# TSAL_Inverters.net
KiCad netlist of a schematic drawn in Altium Designer
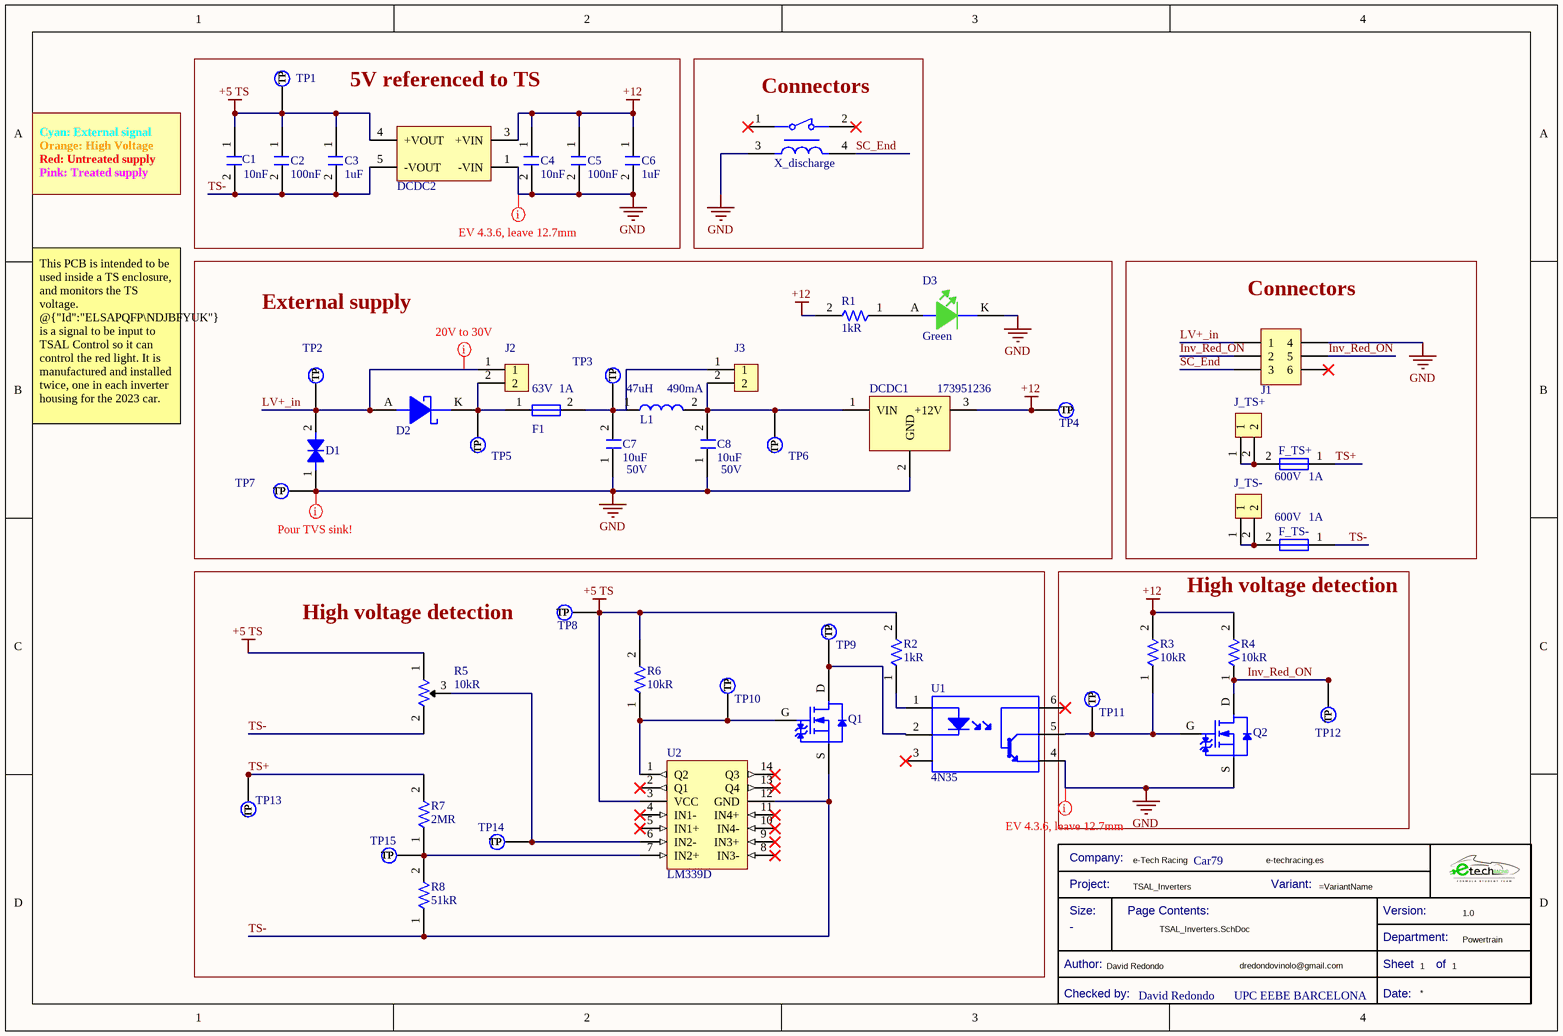
[diagram p0: TSAL_Inverters.SchDoc]

(export (version "E")
  (design (tool "Eeschema 10.0.6"))
  (components
    (comp (ref "*")
      (value "Title Block_template")
      (description "Standard Title Block")
      (fields
        (field (name "SIZE") "-")
        (field (name ".CREATOR") "GP")
        (field (name ".PCBCHECK") "GP")
        (field (name ".SCHCHECK") "GP")
      )
      (libsource (lib "e-Tech_Racing") (part "Title Block_template"))
    )
    (comp (ref "C1")
      (value "885012207092")
      (footprint "C0805FNPC-R")
      (description "Cap, 0.01ΜF, 50V, 10%, X7R, 0805")
      (fields
        (field (name "TOLERANCE") "10%")
        (field (name "CAPACITANCE") "10nF")
        (field (name ".CREATOR") "DR")
      )
      (libsource (lib "Passives") (part "C10n-50V-0805FNPC-X7R"))
    )
    (comp (ref "C2")
      (value "885012207098")
      (footprint "C0805FNPC-R")
      (description "Cap, 0.1ΜF, 50V, 10%, X7R, 0805")
      (fields
        (field (name "TOLERANCE") "10%")
        (field (name "CAPACITANCE") "100nF")
        (field (name ".CREATOR") "DR")
      )
      (libsource (lib "Passives") (part "C100n-50V-0805FNPC-X7R"))
    )
    (comp (ref "C3")
      (value "885012207103")
      (footprint "C0805FNPC-R")
      (fields
        (field (name "TOLERANCE") "10%")
        (field (name "CAPACITANCE") "1uF")
        (field (name ".CREATOR") "GP")
      )
      (libsource (lib "Passives") (part "C1u-50V-0805FNPC-X7R"))
    )
    (comp (ref "C4")
      (value "885012207092")
      (footprint "C0805FNPC-R")
      (description "Cap, 0.01ΜF, 50V, 10%, X7R, 0805")
      (fields
        (field (name "TOLERANCE") "10%")
        (field (name "CAPACITANCE") "10nF")
        (field (name ".CREATOR") "DR")
      )
      (libsource (lib "Passives") (part "C10n-50V-0805FNPC-X7R"))
    )
    (comp (ref "C5")
      (value "885012207098")
      (footprint "C0805FNPC-R")
      (description "Cap, 0.1ΜF, 50V, 10%, X7R, 0805")
      (fields
        (field (name "TOLERANCE") "10%")
        (field (name "CAPACITANCE") "100nF")
        (field (name ".CREATOR") "DR")
      )
      (libsource (lib "Passives") (part "C100n-50V-0805FNPC-X7R"))
    )
    (comp (ref "C6")
      (value "885012207103")
      (footprint "C0805FNPC-R")
      (fields
        (field (name "TOLERANCE") "10%")
        (field (name "CAPACITANCE") "1uF")
        (field (name ".CREATOR") "GP")
      )
      (libsource (lib "Passives") (part "C1u-50V-0805FNPC-X7R"))
    )
    (comp (ref "C7")
      (value "GRJ32ER71H106KE11L")
      (footprint "C10u-50V-1210FNPMLCC-X7R")
      (description "Multilayer Ceramic Capacitors MLCC - SMD/SMT 1210 10uF 50volts X7R +/-10% Soft Term")
      (fields
        (field (name "MANUFACTURER") "Murata")
        (field (name "VOLTAGE RATING") "50V")
        (field (name "TOLERANCE") "10%")
        (field (name "CAPACITANCE") "10uF")
        (field (name ".CREATOR") "DR")
      )
      (libsource (lib "Passives") (part "C10u-50V-1210FNPMLCC-X7R"))
    )
    (comp (ref "C8")
      (value "GRJ32ER71H106KE11L")
      (footprint "C10u-50V-1210FNPMLCC-X7R")
      (description "Multilayer Ceramic Capacitors MLCC - SMD/SMT 1210 10uF 50volts X7R +/-10% Soft Term")
      (fields
        (field (name "MANUFACTURER") "Murata")
        (field (name "VOLTAGE RATING") "50V")
        (field (name "TOLERANCE") "10%")
        (field (name "CAPACITANCE") "10uF")
        (field (name ".CREATOR") "DR")
      )
      (libsource (lib "Passives") (part "C10u-50V-1210FNPMLCC-X7R"))
    )
    (comp (ref "D1")
      (value "824551301")
      (footprint "DTVS-DO-214AB")
      (description "TVS diode [Würth Elektronik] 824551301 TVS diode")
      (fields (field (name "MANUFACTURER") "Wurth Electronics") (field (name ".CREATOR") "DO"))
      (libsource (lib "Filter components") (part "DTVS-40V-DO-214AB"))
    )
    (comp (ref "D2")
      (value "MBR0530")
      (footprint "DSC-SOD123")
      (description "VR=30V IF=500mA 30pF P=410mW")
      (fields (field (name ".CREATOR") "GP"))
      (libsource (lib "Filter components") (part "DSC-0.5/30-SOD123"))
    )
    (comp (ref "D3")
      (value "150080VS75000")
      (footprint "LED_0805_WE")
      (description "Led, Green, 570 Nm, 2 V, 30 Ma, 40 Mcd Rohs Compliant: Yes")
      (fields (field (name "COLOR") "Green") (field (name ".CREATOR") "DR"))
      (libsource (lib "Semiconductor") (part "LEDVS-0805-40"))
    )
    (comp (ref "DCDC1")
      (value "173951236")
      (footprint "DCDC_Magi3c")
      (description "Fdsm Fixed Step Down Regulator M")
      (libsource (lib "Semiconductor") (part "DCDC-36V/12V-0.5A"))
    )
    (comp (ref "DCDC2")
      (value "RNM-1205S/P")
      (footprint "DCDC_RNM-XX05S/P")
      (description "1W DC/DC-Converter 'ECONOLINE' DIP6 1kV unreg; V. In: 12; V. Out: 05; mA. Out: 200")
      (libsource (lib "Semiconductor") (part "DCDC_RNM-1205S/P"))
    )
    (comp (ref "F1")
      (value "0437001.WRA")
      (footprint "Fuse_1206")
      (description "Fuse Chip Fast Acting 1A 63V SMD Solder Pad 1206 Ceramic T/R Automotive")
      (fields
        (field (name "MANUFACTURER") "Littelfuse")
        (field (name "CURRENT RATING") "1A")
        (field (name "VOLTAGE RATING (DC)") "63V")
        (field (name ".CREATOR") "DO")
      )
      (libsource (lib "Filter components") (part "Fuse_1A_63V_1206"))
    )
    (comp (ref "F_TS+")
      (value "485001")
      (footprint "Fuse_485001")
      (description "Surface Mount Fuses 600V 1A Fast Acting")
      (fields
        (field (name "VOLTAGE RATING (DC)") "600V")
        (field (name "CURRENT RATING") "1A")
        (field (name ".CREATOR") "DO")
      )
      (libsource (lib "Filter components") (part "Fuse_1A_600V"))
    )
    (comp (ref "F_TS-")
      (value "485001")
      (footprint "Fuse_485001")
      (description "Surface Mount Fuses 600V 1A Fast Acting")
      (fields
        (field (name "VOLTAGE RATING (DC)") "600V")
        (field (name "CURRENT RATING") "1A")
        (field (name ".CREATOR") "DO")
      )
      (libsource (lib "Filter components") (part "Fuse_1A_600V"))
    )
    (comp (ref "J1")
      (value "J_NanoFit_2x3")
      (footprint "J_NanoFit_2x3")
      (libsource (lib "Electromechanical") (part "J_NanoFit_2x3"))
    )
    (comp (ref "J2")
      (value "61300211121")
      (footprint "J_Pinheader_1x2")
      (description "CONN HEADER 2 POS 2.54")
      (fields (field (name "MANUFACTURER") "Molex") (field (name ".CREATOR") "GP"))
      (libsource (lib "Electromechanical") (part "J_Jumper"))
    )
    (comp (ref "J3")
      (value "61300211121")
      (footprint "J_Pinheader_1x2")
      (description "CONN HEADER 2 POS 2.54")
      (fields (field (name "MANUFACTURER") "Molex") (field (name ".CREATOR") "GP"))
      (libsource (lib "Electromechanical") (part "J_Jumper"))
    )
    (comp (ref "J_TS+")
      (value "436500215")
      (footprint "J_MicroFit_2x1")
      (description "Header 1 Row Vertical Polarizing Peg 2 Pin SMT/Glow Wire Compatible Tin Plate")
      (libsource (lib "Electromechanical") (part "J_MicroFit_2x1"))
    )
    (comp (ref "J_TS-")
      (value "436500215")
      (footprint "J_MicroFit_2x1")
      (description "Header 1 Row Vertical Polarizing Peg 2 Pin SMT/Glow Wire Compatible Tin Plate")
      (libsource (lib "Electromechanical") (part "J_MicroFit_2x1"))
    )
    (comp (ref "L1")
      (value "CDC5D23BNP-470KC")
      (footprint "L_47u-490mA_CF")
      (description "Inductor Power Unshielded Wirewound 47uH 10% 100KHz Ferrite 490mA 546mOhm DCR T/R")
      (fields
        (field (name "MANUFACTURER") "Sumida")
        (field (name "TOLERANCE") "10%")
        (field (name "CURRENT RATING") "490mA")
        (field (name "INDUCTANCE") "47uH")
        (field (name ".CREATOR") "GP")
      )
      (libsource (lib "Passives") (part "L_47u-490mA_CF"))
    )
    (comp (ref "Q1")
      (value "SQ2318BES-T1_GE3")
      (footprint "TRT-NCH-3/35-CPH")
      (description "Automotive N-channel 40 V (d-s) 175C Mosfet SOT-23")
      (fields (field (name ".CREATOR") "DO"))
      (libsource (lib "Semiconductor") (part "TRT-NCH-8/40-SQ"))
    )
    (comp (ref "Q2")
      (value "SQ2318BES-T1_GE3")
      (footprint "TRT-NCH-3/35-CPH")
      (description "Automotive N-channel 40 V (d-s) 175C Mosfet SOT-23")
      (fields (field (name ".CREATOR") "DO"))
      (libsource (lib "Semiconductor") (part "TRT-NCH-8/40-SQ"))
    )
    (comp (ref "R1")
      (value "CR0805-JW-102ELF")
      (footprint "R0805FTK")
      (description "Res Thick Film 0805 1K Ohm 5% 1/8W ±200ppm/°C Molded SMD SMD Paper Tape on Plastic Reel")
      (fields
        (field (name "TOLERANCE") "5%")
        (field (name "RESISTANCE") "1kR")
        (field (name ".CREATOR") "GP")
      )
      (libsource (lib "Passives") (part "R1k-0805FTK"))
    )
    (comp (ref "R2")
      (value "CR0805-JW-102ELF")
      (footprint "R0805FTK")
      (description "Res Thick Film 0805 1K Ohm 5% 1/8W ±200ppm/°C Molded SMD SMD Paper Tape on Plastic Reel")
      (fields
        (field (name "TOLERANCE") "5%")
        (field (name "RESISTANCE") "1kR")
        (field (name ".CREATOR") "GP")
      )
      (libsource (lib "Passives") (part "R1k-0805FTK"))
    )
    (comp (ref "R3")
      (value "CR0805-JW-103ELF")
      (footprint "R0805FTK")
      (fields
        (field (name "TOLERANCE") "5%")
        (field (name "RESISTANCE") "10kR")
        (field (name ".CREATOR") "DR")
      )
      (libsource (lib "Passives") (part "R10k-0805FTK"))
    )
    (comp (ref "R4")
      (value "CR0805-JW-103ELF")
      (footprint "R0805FTK")
      (fields
        (field (name "TOLERANCE") "5%")
        (field (name "RESISTANCE") "10kR")
        (field (name ".CREATOR") "DR")
      )
      (libsource (lib "Passives") (part "R10k-0805FTK"))
    )
    (comp (ref "R5")
      (value "3296W-1-103LF")
      (footprint "R10k-VTR")
      (description "Trimmer, Cermet, Rest 10 Kilohms, PCB, 25 Turns, Pwr-Rtg 0.5W, 3296 Series")
      (fields
        (field (name "MANUFACTURER") "Bourns")
        (field (name "TOLERANCE") "10%")
        (field (name "RESISTANCE") "10kR")
        (field (name ".CREATOR") "DO")
      )
      (libsource (lib "Passives") (part "R10k-VTR"))
    )
    (comp (ref "R6")
      (value "CR0805-JW-103ELF")
      (footprint "R0805FTK")
      (fields
        (field (name "TOLERANCE") "5%")
        (field (name "RESISTANCE") "10kR")
        (field (name ".CREATOR") "DR")
      )
      (libsource (lib "Passives") (part "R10k-0805FTK"))
    )
    (comp (ref "R7")
      (value "R2M-2512FTK")
      (footprint "R2512FTK")
      (description "Current Sense Resistors - SMD 3watts .002ohms 1%")
      (fields
        (field (name "MANUFACTURER") "Vishay Dale")
        (field (name "MANUFACTURER PART NUMBER") "WSLP25122L000FEA")
        (field (name "RESISTANCE") "2MR")
      )
      (libsource (lib "Passives") (part "R2M-2512FTK"))
    )
    (comp (ref "R8")
      (value "CRCW120610K0FKEA")
      (footprint "R1206FTK-W")
      (description "Res Thick Film 1206 51K Ohm 1% 1/4W ±100ppm/°C Molded SMD SMD Punched Carrier T/R")
      (fields
        (field (name "MANUFACTURER") "Panasonic")
        (field (name "MANUFACTURER PART NUMBER") "ERJ-S08F5102V")
        (field (name "RESISTANCE") "51kR")
        (field (name ".CREATOR") "DO")
      )
      (libsource (lib "Passives") (part "R51k-1206FTK"))
    )
    (comp (ref "TP1")
      (value "TestPoint")
      (footprint "TestPoint")
      (description "Test Point 1x1 mm")
      (fields (field (name ".CREATOR") "GP") (field (name ".PCBCHECK") "GP") (field (name ".SCHCHECK") "GP"))
      (libsource (lib "e-Tech_Racing") (part "TestPoint"))
    )
    (comp (ref "TP2")
      (value "TestPoint")
      (footprint "TestPoint")
      (description "Test Point 1x1 mm")
      (fields (field (name ".CREATOR") "GP") (field (name ".PCBCHECK") "GP") (field (name ".SCHCHECK") "GP"))
      (libsource (lib "e-Tech_Racing") (part "TestPoint"))
    )
    (comp (ref "TP3")
      (value "TestPoint")
      (footprint "TestPoint")
      (description "Test Point 1x1 mm")
      (fields (field (name ".CREATOR") "GP") (field (name ".PCBCHECK") "GP") (field (name ".SCHCHECK") "GP"))
      (libsource (lib "e-Tech_Racing") (part "TestPoint"))
    )
    (comp (ref "TP4")
      (value "TestPoint")
      (footprint "TestPoint")
      (description "Test Point 1x1 mm")
      (fields (field (name ".CREATOR") "GP") (field (name ".PCBCHECK") "GP") (field (name ".SCHCHECK") "GP"))
      (libsource (lib "e-Tech_Racing") (part "TestPoint"))
    )
    (comp (ref "TP5")
      (value "TestPoint")
      (footprint "TestPoint")
      (description "Test Point 1x1 mm")
      (fields (field (name ".CREATOR") "GP") (field (name ".PCBCHECK") "GP") (field (name ".SCHCHECK") "GP"))
      (libsource (lib "e-Tech_Racing") (part "TestPoint"))
    )
    (comp (ref "TP6")
      (value "TestPoint")
      (footprint "TestPoint")
      (description "Test Point 1x1 mm")
      (fields (field (name ".CREATOR") "GP") (field (name ".PCBCHECK") "GP") (field (name ".SCHCHECK") "GP"))
      (libsource (lib "e-Tech_Racing") (part "TestPoint"))
    )
    (comp (ref "TP7")
      (value "TestPoint")
      (footprint "TestPoint")
      (description "Test Point 1x1 mm")
      (fields (field (name ".CREATOR") "GP") (field (name ".PCBCHECK") "GP") (field (name ".SCHCHECK") "GP"))
      (libsource (lib "e-Tech_Racing") (part "TestPoint"))
    )
    (comp (ref "TP8")
      (value "TestPoint")
      (footprint "TestPoint")
      (description "Test Point 1x1 mm")
      (fields (field (name ".CREATOR") "GP") (field (name ".PCBCHECK") "GP") (field (name ".SCHCHECK") "GP"))
      (libsource (lib "e-Tech_Racing") (part "TestPoint"))
    )
    (comp (ref "TP9")
      (value "TestPoint")
      (footprint "TestPoint")
      (description "Test Point 1x1 mm")
      (fields (field (name ".CREATOR") "GP") (field (name ".PCBCHECK") "GP") (field (name ".SCHCHECK") "GP"))
      (libsource (lib "e-Tech_Racing") (part "TestPoint"))
    )
    (comp (ref "TP10")
      (value "TestPoint")
      (footprint "TestPoint")
      (description "Test Point 1x1 mm")
      (fields (field (name ".CREATOR") "GP") (field (name ".PCBCHECK") "GP") (field (name ".SCHCHECK") "GP"))
      (libsource (lib "e-Tech_Racing") (part "TestPoint"))
    )
    (comp (ref "TP11")
      (value "TestPoint")
      (footprint "TestPoint")
      (description "Test Point 1x1 mm")
      (fields (field (name ".CREATOR") "GP") (field (name ".PCBCHECK") "GP") (field (name ".SCHCHECK") "GP"))
      (libsource (lib "e-Tech_Racing") (part "TestPoint"))
    )
    (comp (ref "TP12")
      (value "TestPoint")
      (footprint "TestPoint")
      (description "Test Point 1x1 mm")
      (fields (field (name ".CREATOR") "GP") (field (name ".PCBCHECK") "GP") (field (name ".SCHCHECK") "GP"))
      (libsource (lib "e-Tech_Racing") (part "TestPoint"))
    )
    (comp (ref "TP13")
      (value "TestPoint")
      (footprint "TestPoint")
      (description "Test Point 1x1 mm")
      (fields (field (name ".CREATOR") "GP") (field (name ".PCBCHECK") "GP") (field (name ".SCHCHECK") "GP"))
      (libsource (lib "e-Tech_Racing") (part "TestPoint"))
    )
    (comp (ref "TP14")
      (value "TestPoint")
      (footprint "TestPoint")
      (description "Test Point 1x1 mm")
      (fields (field (name ".CREATOR") "GP") (field (name ".PCBCHECK") "GP") (field (name ".SCHCHECK") "GP"))
      (libsource (lib "e-Tech_Racing") (part "TestPoint"))
    )
    (comp (ref "TP15")
      (value "TestPoint")
      (footprint "TestPoint")
      (description "Test Point 1x1 mm")
      (fields (field (name ".CREATOR") "GP") (field (name ".PCBCHECK") "GP") (field (name ".SCHCHECK") "GP"))
      (libsource (lib "e-Tech_Racing") (part "TestPoint"))
    )
    (comp (ref "U1")
      (value "4N35")
      (footprint "Optocoupler_4N35")
      (description "Optocoupler DC-IN 1-CH Transistor With Base DC-OUT 6-Pin PDIP SMD T/R")
      (fields
        (field (name "MANUFACTURER") "Vishay Lite-On")
        (field (name "MANUFACTURER PART NUMBER") "CNY17-4S-TA1")
        (field (name ".CREATOR") "DO")
      )
      (libsource (lib "Semiconductor") (part "Optocoupler_4N35"))
    )
    (comp (ref "U2")
      (value "LM339D")
      (footprint "Array_4_Amp_LM339D")
      (description "Comparator Quad ±18V/36V 14-Pin SOIC Tube")
      (fields
        (field (name "MANUFACTURER") "Texas Instruments")
        (field (name "MANUFACTURER PART NUMBER") "LM339D")
        (field (name ".CREATOR") "DO")
      )
      (libsource (lib "Integrated circuits") (part "Array_4_Amp_LM339D"))
    )
    (comp (ref "X_discharge")
      (value "DBR72410FU")
      (footprint "Relay_DAR72410FU")
      (description "Relay, Reed Switch, SPNC, Rhodium Cntcts, 24VDC, 10kV Isol., PCB Mnt/Coil Conn./FL HV")
      (fields (field (name "MANUFACTURER") "Cynergy3") (field (name "MANUFACTURER PART NUMBER") "DBR72410F"))
      (libsource (lib "Electromechanical") (part "Relay_DBR72410FU"))
    )
  )
  (nets
    (net (code "1") (name "+5 TS") (class "Default")
      (node (ref "C1") (pin "1") (pinfunction "1_1") (pintype "passive"))
      (node (ref "C2") (pin "1") (pinfunction "1_1") (pintype "passive"))
      (node (ref "C3") (pin "1") (pinfunction "1_1") (pintype "passive"))
      (node (ref "DCDC2") (pin "4") (pinfunction "+VOUT_4") (pintype "passive"))
      (node (ref "R2") (pin "2") (pinfunction "2_2") (pintype "passive"))
      (node (ref "R5") (pin "1") (pinfunction "2_1") (pintype "passive"))
      (node (ref "R6") (pin "2") (pinfunction "2_2") (pintype "passive"))
      (node (ref "TP1") (pin "1") (pinfunction "TP_1") (pintype "passive"))
      (node (ref "TP8") (pin "1") (pinfunction "TP_1") (pintype "passive"))
      (node (ref "U2") (pin "3") (pinfunction "VCC_3") (pintype "power_in"))
    )
    (net (code "2") (name "+12") (class "Default")
      (node (ref "C4") (pin "1") (pinfunction "1_1") (pintype "passive"))
      (node (ref "C5") (pin "1") (pinfunction "1_1") (pintype "passive"))
      (node (ref "C6") (pin "1") (pinfunction "1_1") (pintype "passive"))
      (node (ref "DCDC1") (pin "3") (pinfunction "+12V_3") (pintype "passive"))
      (node (ref "DCDC2") (pin "3") (pinfunction "+VIN_3") (pintype "passive"))
      (node (ref "R1") (pin "2") (pinfunction "2_2") (pintype "passive"))
      (node (ref "R3") (pin "2") (pinfunction "2_2") (pintype "passive"))
      (node (ref "R4") (pin "2") (pinfunction "2_2") (pintype "passive"))
      (node (ref "TP4") (pin "1") (pinfunction "TP_1") (pintype "passive"))
    )
    (net (code "3") (name "/Inv_Red_ON") (class "Default")
      (node (ref "J1") (pin "2") (pinfunction "2_2") (pintype "passive"))
      (node (ref "J1") (pin "5") (pinfunction "5_5") (pintype "passive"))
      (node (ref "Q2") (pin "D") (pinfunction "D_D") (pintype "passive"))
      (node (ref "R4") (pin "1") (pinfunction "1_1") (pintype "passive"))
      (node (ref "TP12") (pin "1") (pinfunction "TP_1") (pintype "passive"))
    )
    (net (code "4") (name "/LV+_in") (class "Default")
      (node (ref "D1") (pin "2") (pinfunction "2_2") (pintype "passive"))
      (node (ref "D2") (pin "A") (pinfunction "A_A") (pintype "passive"))
      (node (ref "J1") (pin "1") (pinfunction "1_1") (pintype "passive"))
      (node (ref "J2") (pin "1") (pinfunction "1_1") (pintype "passive"))
      (node (ref "TP2") (pin "1") (pinfunction "TP_1") (pintype "passive"))
    )
    (net (code "5") (name "/SC_End") (class "Default")
      (node (ref "J1") (pin "3") (pinfunction "3_3") (pintype "passive"))
      (node (ref "X_discharge") (pin "4") (pinfunction "4_4") (pintype "passive"))
    )
    (net (code "6") (name "/TS+") (class "Default")
      (node (ref "F_TS+") (pin "1") (pinfunction "1_1") (pintype "passive"))
      (node (ref "R7") (pin "2") (pinfunction "2_2") (pintype "passive"))
      (node (ref "TP13") (pin "1") (pinfunction "TP_1") (pintype "passive"))
    )
    (net (code "7") (name "/TS-") (class "Default")
      (node (ref "C1") (pin "2") (pinfunction "2_2") (pintype "passive"))
      (node (ref "C2") (pin "2") (pinfunction "2_2") (pintype "passive"))
      (node (ref "C3") (pin "2") (pinfunction "2_2") (pintype "passive"))
      (node (ref "DCDC2") (pin "5") (pinfunction "-VOUT_5") (pintype "passive"))
      (node (ref "F_TS-") (pin "1") (pinfunction "1_1") (pintype "passive"))
      (node (ref "Q1") (pin "S") (pinfunction "S_S") (pintype "passive"))
      (node (ref "R5") (pin "2") (pinfunction "2_2") (pintype "passive"))
      (node (ref "R8") (pin "1") (pinfunction "1_1") (pintype "passive"))
      (node (ref "U2") (pin "12") (pinfunction "GND_12") (pintype "power_in"))
    )
    (net (code "8") (name "GND") (class "Default")
      (node (ref "C4") (pin "2") (pinfunction "2_2") (pintype "passive"))
      (node (ref "C5") (pin "2") (pinfunction "2_2") (pintype "passive"))
      (node (ref "C6") (pin "2") (pinfunction "2_2") (pintype "passive"))
      (node (ref "C7") (pin "1") (pinfunction "1_1") (pintype "passive"))
      (node (ref "C8") (pin "1") (pinfunction "1_1") (pintype "passive"))
      (node (ref "D1") (pin "1") (pinfunction "1_1") (pintype "passive"))
      (node (ref "D3") (pin "K") (pinfunction "K_K") (pintype "passive"))
      (node (ref "DCDC1") (pin "2") (pinfunction "GND_2") (pintype "passive"))
      (node (ref "DCDC2") (pin "1") (pinfunction "-VIN_1") (pintype "passive"))
      (node (ref "J1") (pin "4") (pinfunction "4_4") (pintype "passive"))
      (node (ref "Q2") (pin "S") (pinfunction "S_S") (pintype "passive"))
      (node (ref "TP7") (pin "1") (pinfunction "TP_1") (pintype "passive"))
      (node (ref "U1") (pin "4") (pinfunction "E_4") (pintype "passive"))
      (node (ref "X_discharge") (pin "3") (pinfunction "3_3") (pintype "passive"))
    )
    (net (code "9") (name "Net-(D3-PadA)") (class "Default")
      (node (ref "D3") (pin "A") (pinfunction "A_A") (pintype "passive"))
      (node (ref "R1") (pin "1") (pinfunction "1_1") (pintype "passive"))
    )
    (net (code "10") (name "Net-(DCDC1-VIN)") (class "Default")
      (node (ref "C8") (pin "2") (pinfunction "2_2") (pintype "passive"))
      (node (ref "DCDC1") (pin "1") (pinfunction "VIN_1") (pintype "passive"))
      (node (ref "J3") (pin "2") (pinfunction "2_2") (pintype "passive"))
      (node (ref "L1") (pin "2") (pinfunction "2_2") (pintype "passive"))
      (node (ref "TP6") (pin "1") (pinfunction "TP_1") (pintype "passive"))
    )
    (net (code "11") (name "Net-(F_TS+-Pad2)") (class "Default")
      (node (ref "F_TS+") (pin "2") (pinfunction "2_2") (pintype "passive"))
      (node (ref "J_TS+") (pin "1") (pinfunction "1_1") (pintype "passive"))
      (node (ref "J_TS+") (pin "2") (pinfunction "2_2") (pintype "passive"))
    )
    (net (code "12") (name "Net-(F_TS--Pad2)") (class "Default")
      (node (ref "F_TS-") (pin "2") (pinfunction "2_2") (pintype "passive"))
      (node (ref "J_TS-") (pin "1") (pinfunction "1_1") (pintype "passive"))
      (node (ref "J_TS-") (pin "2") (pinfunction "2_2") (pintype "passive"))
    )
    (net (code "13") (name "Net-(TP3-TP)") (class "Default")
      (node (ref "C7") (pin "2") (pinfunction "2_2") (pintype "passive"))
      (node (ref "F1") (pin "2") (pinfunction "2_2") (pintype "passive"))
      (node (ref "J3") (pin "1") (pinfunction "1_1") (pintype "passive"))
      (node (ref "L1") (pin "1") (pinfunction "1_1") (pintype "passive"))
      (node (ref "TP3") (pin "1") (pinfunction "TP_1") (pintype "passive"))
    )
    (net (code "14") (name "Net-(TP5-TP)") (class "Default")
      (node (ref "D2") (pin "K") (pinfunction "K_K") (pintype "passive"))
      (node (ref "F1") (pin "1") (pinfunction "1_1") (pintype "passive"))
      (node (ref "J2") (pin "2") (pinfunction "2_2") (pintype "passive"))
      (node (ref "TP5") (pin "1") (pinfunction "TP_1") (pintype "passive"))
    )
    (net (code "15") (name "Net-(TP9-TP)") (class "Default")
      (node (ref "Q1") (pin "D") (pinfunction "D_D") (pintype "passive"))
      (node (ref "TP9") (pin "1") (pinfunction "TP_1") (pintype "passive"))
      (node (ref "U1") (pin "2") (pinfunction "K_2") (pintype "passive"))
    )
    (net (code "16") (name "Net-(TP10-TP)") (class "Default")
      (node (ref "Q1") (pin "G") (pinfunction "G_G") (pintype "passive"))
      (node (ref "R6") (pin "1") (pinfunction "1_1") (pintype "passive"))
      (node (ref "TP10") (pin "1") (pinfunction "TP_1") (pintype "passive"))
      (node (ref "U2") (pin "1") (pinfunction "Q2_1") (pintype "output"))
    )
    (net (code "17") (name "Net-(TP11-TP)") (class "Default")
      (node (ref "Q2") (pin "G") (pinfunction "G_G") (pintype "passive"))
      (node (ref "R3") (pin "1") (pinfunction "1_1") (pintype "passive"))
      (node (ref "TP11") (pin "1") (pinfunction "TP_1") (pintype "passive"))
      (node (ref "U1") (pin "5") (pinfunction "E_5") (pintype "passive"))
    )
    (net (code "18") (name "Net-(TP14-TP)") (class "Default")
      (node (ref "R5") (pin "3") (pinfunction "3_3") (pintype "passive"))
      (node (ref "TP14") (pin "1") (pinfunction "TP_1") (pintype "passive"))
      (node (ref "U2") (pin "6") (pinfunction "IN2-_6") (pintype "input"))
    )
    (net (code "19") (name "Net-(TP15-TP)") (class "Default")
      (node (ref "R7") (pin "1") (pinfunction "1_1") (pintype "passive"))
      (node (ref "R8") (pin "2") (pinfunction "2_2") (pintype "passive"))
      (node (ref "TP15") (pin "1") (pinfunction "TP_1") (pintype "passive"))
      (node (ref "U2") (pin "7") (pinfunction "IN2+_7") (pintype "input"))
    )
    (net (code "20") (name "Net-(U1-A)") (class "Default")
      (node (ref "R2") (pin "1") (pinfunction "1_1") (pintype "passive"))
      (node (ref "U1") (pin "1") (pinfunction "A_1") (pintype "passive"))
    )
    (net (code "21") (name "unconnected-(J1-Pad6)") (class "Default")
      (node (ref "J1") (pin "6") (pinfunction "6_6") (pintype "passive+no_connect"))
    )
    (net (code "22") (name "unconnected-(U1-C-Pad3)") (class "Default")
      (node (ref "U1") (pin "3") (pinfunction "C_3") (pintype "passive+no_connect"))
    )
    (net (code "23") (name "unconnected-(U1-E-Pad6)") (class "Default")
      (node (ref "U1") (pin "6") (pinfunction "E_6") (pintype "passive+no_connect"))
    )
    (net (code "24") (name "unconnected-(U2-IN1+-Pad5)") (class "Default")
      (node (ref "U2") (pin "5") (pinfunction "IN1+_5") (pintype "input+no_connect"))
    )
    (net (code "25") (name "unconnected-(U2-IN1--Pad4)") (class "Default")
      (node (ref "U2") (pin "4") (pinfunction "IN1-_4") (pintype "input+no_connect"))
    )
    (net (code "26") (name "unconnected-(U2-IN3+-Pad9)") (class "Default")
      (node (ref "U2") (pin "9") (pinfunction "IN3+_9") (pintype "input+no_connect"))
    )
    (net (code "27") (name "unconnected-(U2-IN3--Pad8)") (class "Default")
      (node (ref "U2") (pin "8") (pinfunction "IN3-_8") (pintype "input+no_connect"))
    )
    (net (code "28") (name "unconnected-(U2-IN4+-Pad11)") (class "Default")
      (node (ref "U2") (pin "11") (pinfunction "IN4+_11") (pintype "input+no_connect"))
    )
    (net (code "29") (name "unconnected-(U2-IN4--Pad10)") (class "Default")
      (node (ref "U2") (pin "10") (pinfunction "IN4-_10") (pintype "input+no_connect"))
    )
    (net (code "30") (name "unconnected-(U2-Q1-Pad2)") (class "Default")
      (node (ref "U2") (pin "2") (pinfunction "Q1_2") (pintype "output+no_connect"))
    )
    (net (code "31") (name "unconnected-(U2-Q3-Pad14)") (class "Default")
      (node (ref "U2") (pin "14") (pinfunction "Q3_14") (pintype "output+no_connect"))
    )
    (net (code "32") (name "unconnected-(U2-Q4-Pad13)") (class "Default")
      (node (ref "U2") (pin "13") (pinfunction "Q4_13") (pintype "output+no_connect"))
    )
    (net (code "33") (name "unconnected-(X_discharge-Pad1)") (class "Default")
      (node (ref "X_discharge") (pin "1") (pinfunction "1_1") (pintype "passive+no_connect"))
    )
    (net (code "34") (name "unconnected-(X_discharge-Pad2)") (class "Default")
      (node (ref "X_discharge") (pin "2") (pinfunction "2_2") (pintype "passive+no_connect"))
    )
  )
)
